# HAS.net
KiCad netlist of a schematic drawn in EAGLE
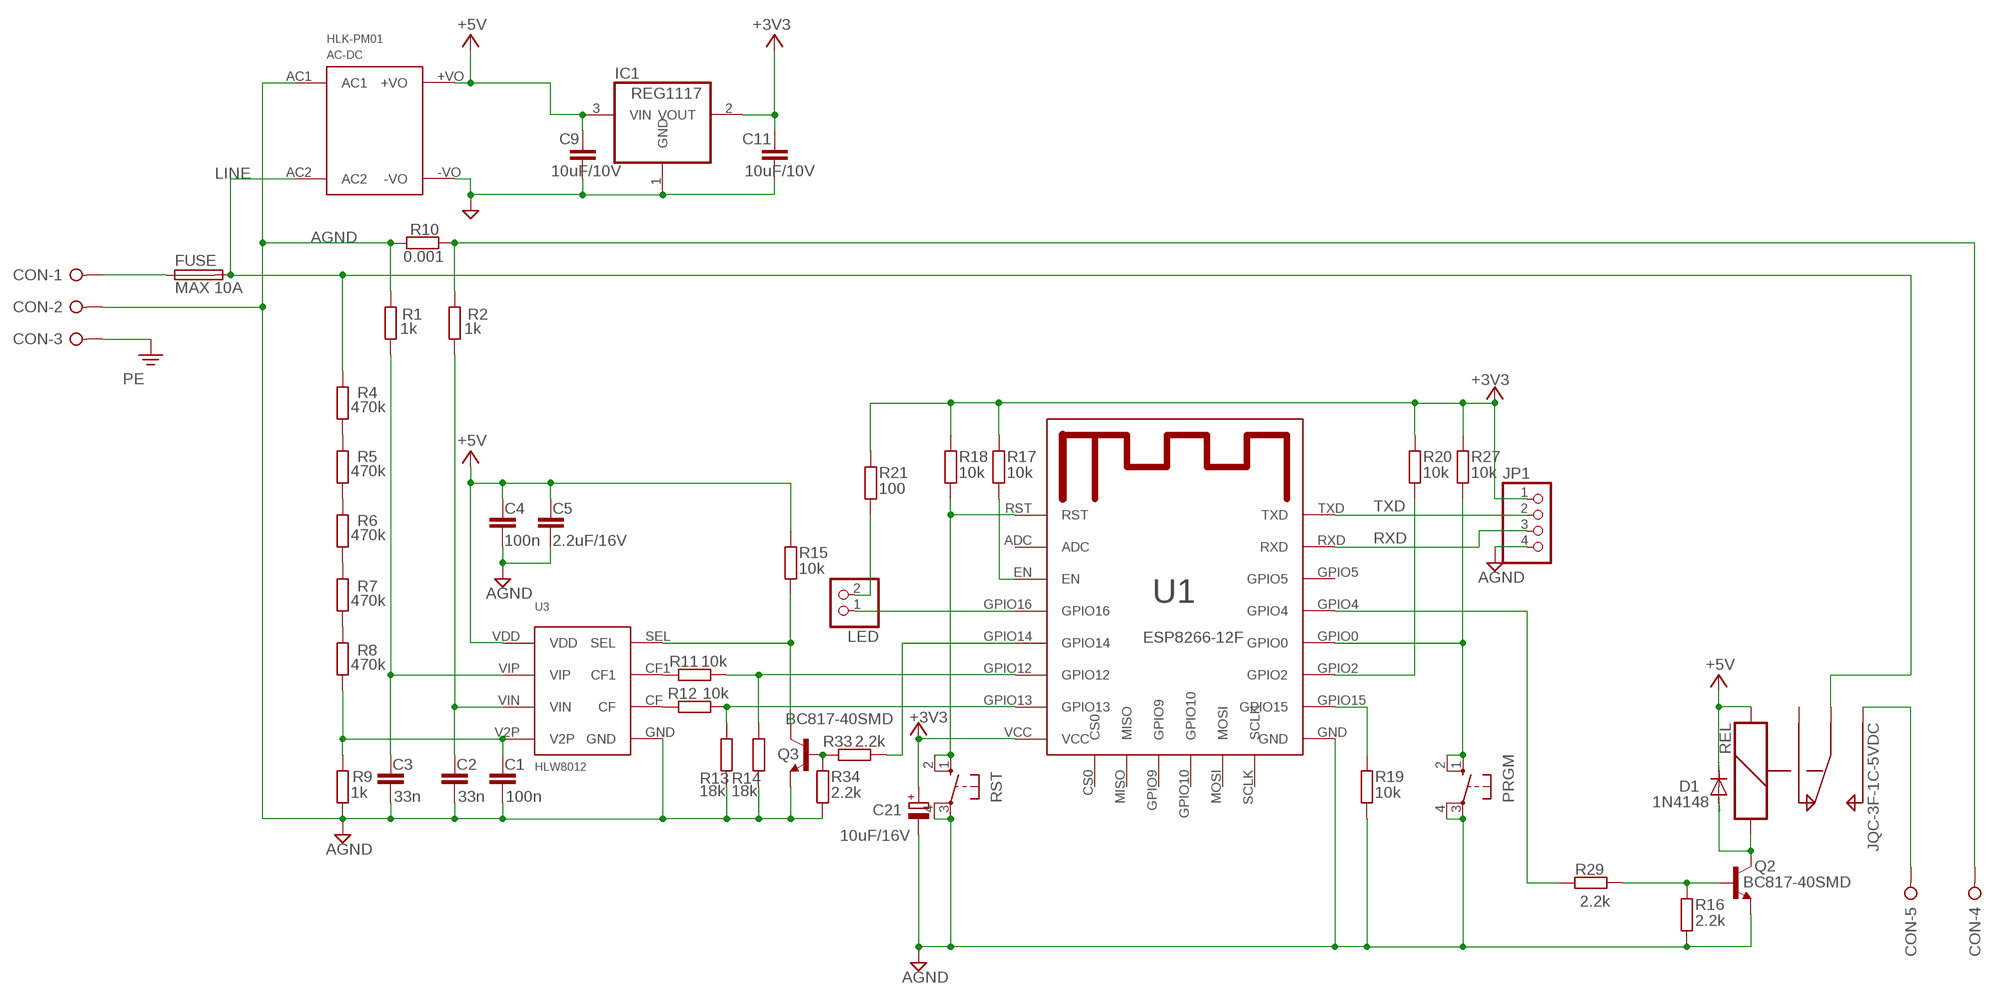
[diagram p0: schematic, sheet 1]

(export (version "E")
  (design (tool "Eeschema 10.0.6"))
  (components
    (comp (ref "AC-DC")
      (value "HLK-PM01")
      (footprint "eagle-import:HLK-PM01")
      (libsource (lib "eagle-import") (part "HLK-PM01"))
    )
    (comp (ref "C1")
      (value "100n")
      (footprint "eagle-import:C0805")
      (libsource (lib "eagle-import") (part "C0805"))
    )
    (comp (ref "C2")
      (value "33n")
      (footprint "eagle-import:C0805")
      (libsource (lib "eagle-import") (part "C0805"))
    )
    (comp (ref "C3")
      (value "33n")
      (footprint "eagle-import:C0805")
      (libsource (lib "eagle-import") (part "C0805"))
    )
    (comp (ref "C4")
      (value "100n")
      (footprint "eagle-import:C0805")
      (libsource (lib "eagle-import") (part "C0805"))
    )
    (comp (ref "C5")
      (value "2.2uF/16V")
      (footprint "eagle-import:C0805")
      (libsource (lib "eagle-import") (part "C0805"))
    )
    (comp (ref "C9")
      (value "10uF/10V")
      (footprint "eagle-import:C1206")
      (libsource (lib "eagle-import") (part "C1206"))
    )
    (comp (ref "C11")
      (value "10uF/10V")
      (footprint "eagle-import:C1206")
      (libsource (lib "eagle-import") (part "C1206"))
    )
    (comp (ref "C21")
      (value "10uF/16V")
      (footprint "eagle-import:SMC_B")
      (libsource (lib "eagle-import") (part "TANT_B"))
    )
    (comp (ref "CON")
      (value "W237-05P")
      (footprint "eagle-import:W237-5P")
      (libsource (lib "eagle-import") (part "W237-05P"))
    )
    (comp (ref "D1")
      (value "1N4148")
      (footprint "eagle-import:SOD123")
      (libsource (lib "eagle-import") (part "DIODE-SOD123"))
    )
    (comp (ref "FUSE")
      (value "MAX 10A")
      (footprint "eagle-import:SH22")
      (libsource (lib "eagle-import") (part "FUSE"))
    )
    (comp (ref "IC1")
      (value "REG1117")
      (footprint "eagle-import:SOT223")
      (libsource (lib "eagle-import") (part "REG1117"))
    )
    (comp (ref "JP1")
      (value "PINHD-1X4")
      (footprint "eagle-import:1X04")
      (libsource (lib "eagle-import") (part "PINHD-1X4"))
    )
    (comp (ref "LED")
      (value "PINHD-1X2")
      (footprint "eagle-import:1X02")
      (libsource (lib "eagle-import") (part "PINHD-1X2"))
    )
    (comp (ref "PRGM")
      (value "10-XX")
      (footprint "eagle-import:B3F-10XX")
      (fields (field (name "MPN") "B3F-1000"))
      (libsource (lib "eagle-import") (part "10-XX"))
    )
    (comp (ref "Q2")
      (value "BC817-40SMD")
      (footprint "eagle-import:SOT23-BEC")
      (libsource (lib "eagle-import") (part "BC817SMD-40"))
    )
    (comp (ref "Q3")
      (value "BC817-40SMD")
      (footprint "eagle-import:SOT23-BEC")
      (libsource (lib "eagle-import") (part "BC817SMD-40"))
    )
    (comp (ref "R1")
      (value "1k")
      (footprint "eagle-import:R0805")
      (libsource (lib "eagle-import") (part "R0805"))
    )
    (comp (ref "R2")
      (value "1k")
      (footprint "eagle-import:R0805")
      (libsource (lib "eagle-import") (part "R0805"))
    )
    (comp (ref "R4")
      (value "470k")
      (footprint "eagle-import:R0805")
      (libsource (lib "eagle-import") (part "R0805"))
    )
    (comp (ref "R5")
      (value "470k")
      (footprint "eagle-import:R0805")
      (libsource (lib "eagle-import") (part "R0805"))
    )
    (comp (ref "R6")
      (value "470k")
      (footprint "eagle-import:R0805")
      (libsource (lib "eagle-import") (part "R0805"))
    )
    (comp (ref "R7")
      (value "470k")
      (footprint "eagle-import:R0805")
      (libsource (lib "eagle-import") (part "R0805"))
    )
    (comp (ref "R8")
      (value "470k")
      (footprint "eagle-import:R0805")
      (libsource (lib "eagle-import") (part "R0805"))
    )
    (comp (ref "R9")
      (value "1k")
      (footprint "eagle-import:R0805")
      (libsource (lib "eagle-import") (part "R0805"))
    )
    (comp (ref "R10")
      (value "0.001")
      (footprint "eagle-import:R2512")
      (fields (field (name "SPICEPREFIX") "R"))
      (libsource (lib "eagle-import") (part "R2512"))
    )
    (comp (ref "R11")
      (value "10k")
      (footprint "eagle-import:R0805")
      (libsource (lib "eagle-import") (part "R0805"))
    )
    (comp (ref "R12")
      (value "10k")
      (footprint "eagle-import:R0805")
      (libsource (lib "eagle-import") (part "R0805"))
    )
    (comp (ref "R13")
      (value "18k")
      (footprint "eagle-import:R0805")
      (libsource (lib "eagle-import") (part "R0805"))
    )
    (comp (ref "R14")
      (value "18k")
      (footprint "eagle-import:R0805")
      (fields (field (name "SPICEPREFIX") "R"))
      (libsource (lib "eagle-import") (part "R0805"))
    )
    (comp (ref "R15")
      (value "10k")
      (footprint "eagle-import:R0805")
      (fields (field (name "SPICEPREFIX") "R"))
      (libsource (lib "eagle-import") (part "R0805"))
    )
    (comp (ref "R16")
      (value "2.2k")
      (footprint "eagle-import:R0805")
      (fields (field (name "SPICEPREFIX") "R"))
      (libsource (lib "eagle-import") (part "R0805"))
    )
    (comp (ref "R17")
      (value "10k")
      (footprint "eagle-import:R0805")
      (fields (field (name "SPICEPREFIX") "R"))
      (libsource (lib "eagle-import") (part "R0805"))
    )
    (comp (ref "R18")
      (value "10k")
      (footprint "eagle-import:R0805")
      (fields (field (name "SPICEPREFIX") "R"))
      (libsource (lib "eagle-import") (part "R0805"))
    )
    (comp (ref "R19")
      (value "10k")
      (footprint "eagle-import:R0805")
      (fields (field (name "SPICEPREFIX") "R"))
      (libsource (lib "eagle-import") (part "R0805"))
    )
    (comp (ref "R20")
      (value "10k")
      (footprint "eagle-import:R0805")
      (fields (field (name "SPICEPREFIX") "R"))
      (libsource (lib "eagle-import") (part "R0805"))
    )
    (comp (ref "R21")
      (value "100")
      (footprint "eagle-import:R0805")
      (fields (field (name "SPICEPREFIX") "R"))
      (libsource (lib "eagle-import") (part "R0805"))
    )
    (comp (ref "R27")
      (value "10k")
      (footprint "eagle-import:R0805")
      (fields (field (name "SPICEPREFIX") "R"))
      (libsource (lib "eagle-import") (part "R0805"))
    )
    (comp (ref "R29")
      (value "2.2k")
      (footprint "eagle-import:R0805")
      (fields (field (name "SPICEPREFIX") "R"))
      (libsource (lib "eagle-import") (part "R0805"))
    )
    (comp (ref "R33")
      (value "2.2k")
      (footprint "eagle-import:R0805")
      (fields (field (name "SPICEPREFIX") "R"))
      (libsource (lib "eagle-import") (part "R0805"))
    )
    (comp (ref "R34")
      (value "2.2k")
      (footprint "eagle-import:R0805")
      (fields (field (name "SPICEPREFIX") "R"))
      (libsource (lib "eagle-import") (part "R0805"))
    )
    (comp (ref "REL")
      (value "JQC-3F-1C-5VDC")
      (footprint "eagle-import:JQC-3F-1C-5VDC")
      (libsource (lib "eagle-import") (part "JQC-3F-1C-5VDC"))
    )
    (comp (ref "RST")
      (value "10-XX")
      (footprint "eagle-import:B3F-10XX")
      (fields (field (name "MPN") "B3F-1000"))
      (libsource (lib "eagle-import") (part "10-XX"))
    )
    (comp (ref "U1")
      (value "ESP8266-12F")
      (footprint "eagle-import:ESP8266-12F")
      (libsource (lib "eagle-import") (part "ESP8266-12F"))
    )
    (comp (ref "U3")
      (value "HLW8012")
      (footprint "eagle-import:HLW8012")
      (libsource (lib "eagle-import") (part "HLW8012"))
    )
  )
  (nets
    (net (code "1") (name "+3V3") (class "Default")
      (node (ref "C11") (pin "2") (pinfunction "2_2") (pintype "passive"))
      (node (ref "C21") (pin "+") (pinfunction "+_+") (pintype "passive"))
      (node (ref "IC1") (pin "2") (pinfunction "VOUT_2") (pintype "output"))
      (node (ref "JP1") (pin "1") (pinfunction "1_1") (pintype "passive"))
      (node (ref "R17") (pin "1") (pinfunction "1_1") (pintype "passive"))
      (node (ref "R18") (pin "1") (pinfunction "1_1") (pintype "passive"))
      (node (ref "R20") (pin "1") (pinfunction "1_1") (pintype "passive"))
      (node (ref "R21") (pin "1") (pinfunction "1_1") (pintype "passive"))
      (node (ref "R27") (pin "1") (pinfunction "1_1") (pintype "passive"))
      (node (ref "U1") (pin "VCC") (pinfunction "VCC_VCC") (pintype "bidirectional"))
    )
    (net (code "2") (name "+5V") (class "Default")
      (node (ref "AC-DC") (pin "+VO") (pinfunction "+VO_+VO") (pintype "bidirectional"))
      (node (ref "C4") (pin "1") (pinfunction "1_1") (pintype "passive"))
      (node (ref "C5") (pin "1") (pinfunction "1_1") (pintype "passive"))
      (node (ref "C9") (pin "2") (pinfunction "2_2") (pintype "passive"))
      (node (ref "D1") (pin "C") (pinfunction "C_C") (pintype "passive"))
      (node (ref "IC1") (pin "3") (pinfunction "VIN_3") (pintype "input"))
      (node (ref "R15") (pin "1") (pinfunction "1_1") (pintype "passive"))
      (node (ref "REL") (pin "R2") (pinfunction "R2_R2") (pintype "passive"))
      (node (ref "U3") (pin "VDD") (pinfunction "VDD_VDD") (pintype "bidirectional"))
    )
    (net (code "3") (name "/LINE") (class "Default")
      (node (ref "AC-DC") (pin "AC2") (pinfunction "AC2_AC2") (pintype "bidirectional"))
      (node (ref "FUSE") (pin "2") (pinfunction "2_2") (pintype "passive"))
      (node (ref "R4") (pin "2") (pinfunction "2_2") (pintype "passive"))
      (node (ref "REL") (pin "COM") (pinfunction "COM_COM") (pintype "passive"))
    )
    (net (code "4") (name "/RXD") (class "Default")
      (node (ref "JP1") (pin "3") (pinfunction "3_3") (pintype "passive"))
      (node (ref "U1") (pin "RXD") (pinfunction "RXD_RXD") (pintype "bidirectional"))
    )
    (net (code "5") (name "/TXD") (class "Default")
      (node (ref "JP1") (pin "2") (pinfunction "2_2") (pintype "passive"))
      (node (ref "U1") (pin "TXD") (pinfunction "TXD_TXD") (pintype "bidirectional"))
    )
    (net (code "6") (name "AGND") (class "Default")
      (node (ref "AC-DC") (pin "-VO") (pinfunction "-VO_-VO") (pintype "bidirectional"))
      (node (ref "AC-DC") (pin "AC1") (pinfunction "AC1_AC1") (pintype "bidirectional"))
      (node (ref "C1") (pin "2") (pinfunction "2_2") (pintype "passive"))
      (node (ref "C11") (pin "1") (pinfunction "1_1") (pintype "passive"))
      (node (ref "C2") (pin "2") (pinfunction "2_2") (pintype "passive"))
      (node (ref "C21") (pin "-") (pinfunction "-_-") (pintype "passive"))
      (node (ref "C3") (pin "2") (pinfunction "2_2") (pintype "passive"))
      (node (ref "C4") (pin "2") (pinfunction "2_2") (pintype "passive"))
      (node (ref "C5") (pin "2") (pinfunction "2_2") (pintype "passive"))
      (node (ref "C9") (pin "1") (pinfunction "1_1") (pintype "passive"))
      (node (ref "CON") (pin "2") (pinfunction "KL_2") (pintype "passive"))
      (node (ref "IC1") (pin "1") (pinfunction "GND_1") (pintype "power_in"))
      (node (ref "JP1") (pin "4") (pinfunction "4_4") (pintype "passive"))
      (node (ref "PRGM") (pin "3") (pinfunction "P_3") (pintype "passive"))
      (node (ref "PRGM") (pin "4") (pinfunction "P1_4") (pintype "passive"))
      (node (ref "Q2") (pin "E") (pinfunction "E_E") (pintype "passive"))
      (node (ref "Q3") (pin "E") (pinfunction "E_E") (pintype "passive"))
      (node (ref "R1") (pin "1") (pinfunction "1_1") (pintype "passive"))
      (node (ref "R10") (pin "1") (pinfunction "1_1") (pintype "passive"))
      (node (ref "R13") (pin "2") (pinfunction "2_2") (pintype "passive"))
      (node (ref "R14") (pin "2") (pinfunction "2_2") (pintype "passive"))
      (node (ref "R16") (pin "2") (pinfunction "2_2") (pintype "passive"))
      (node (ref "R19") (pin "2") (pinfunction "2_2") (pintype "passive"))
      (node (ref "R34") (pin "2") (pinfunction "2_2") (pintype "passive"))
      (node (ref "R9") (pin "1") (pinfunction "1_1") (pintype "passive"))
      (node (ref "RST") (pin "3") (pinfunction "P_3") (pintype "passive"))
      (node (ref "RST") (pin "4") (pinfunction "P1_4") (pintype "passive"))
      (node (ref "U1") (pin "GND") (pinfunction "GND_GND") (pintype "bidirectional"))
      (node (ref "U3") (pin "GND") (pinfunction "GND_GND") (pintype "bidirectional"))
    )
    (net (code "7") (name "Net-(C1-Pad1)") (class "Default")
      (node (ref "C1") (pin "1") (pinfunction "1_1") (pintype "passive"))
      (node (ref "R8") (pin "1") (pinfunction "1_1") (pintype "passive"))
      (node (ref "R9") (pin "2") (pinfunction "2_2") (pintype "passive"))
      (node (ref "U3") (pin "V2P") (pinfunction "V2P_V2P") (pintype "bidirectional"))
    )
    (net (code "8") (name "Net-(C2-Pad1)") (class "Default")
      (node (ref "C2") (pin "1") (pinfunction "1_1") (pintype "passive"))
      (node (ref "R2") (pin "2") (pinfunction "2_2") (pintype "passive"))
      (node (ref "U3") (pin "VIN") (pinfunction "VIN_VIN") (pintype "bidirectional"))
    )
    (net (code "9") (name "Net-(C3-Pad1)") (class "Default")
      (node (ref "C3") (pin "1") (pinfunction "1_1") (pintype "passive"))
      (node (ref "R1") (pin "2") (pinfunction "2_2") (pintype "passive"))
      (node (ref "U3") (pin "VIP") (pinfunction "VIP_VIP") (pintype "bidirectional"))
    )
    (net (code "10") (name "Net-(CONA-KL)") (class "Default")
      (node (ref "CON") (pin "1") (pinfunction "KL_1") (pintype "passive"))
      (node (ref "FUSE") (pin "1") (pinfunction "1_1") (pintype "passive"))
    )
    (net (code "11") (name "Net-(COND-KL)") (class "Default")
      (node (ref "CON") (pin "4") (pinfunction "KL_4") (pintype "passive"))
      (node (ref "R10") (pin "2") (pinfunction "2_2") (pintype "passive"))
      (node (ref "R2") (pin "1") (pinfunction "1_1") (pintype "passive"))
    )
    (net (code "12") (name "Net-(CONE-KL)") (class "Default")
      (node (ref "CON") (pin "5") (pinfunction "KL_5") (pintype "passive"))
      (node (ref "REL") (pin "NO") (pinfunction "NO_NO") (pintype "passive"))
    )
    (net (code "13") (name "Net-(D1-PadA)") (class "Default")
      (node (ref "D1") (pin "A") (pinfunction "A_A") (pintype "passive"))
      (node (ref "Q2") (pin "C") (pinfunction "C_C") (pintype "passive"))
      (node (ref "REL") (pin "R1") (pinfunction "R1_R1") (pintype "passive"))
    )
    (net (code "14") (name "Net-(LED-Pad1)") (class "Default")
      (node (ref "LED") (pin "1") (pinfunction "1_1") (pintype "passive"))
      (node (ref "U1") (pin "GPIO16") (pinfunction "GPIO16_GPIO16") (pintype "bidirectional"))
    )
    (net (code "15") (name "Net-(LED-Pad2)") (class "Default")
      (node (ref "LED") (pin "2") (pinfunction "2_2") (pintype "passive"))
      (node (ref "R21") (pin "2") (pinfunction "2_2") (pintype "passive"))
    )
    (net (code "16") (name "Net-(PRGM-S)") (class "Default")
      (node (ref "PRGM") (pin "1") (pinfunction "S_1") (pintype "passive"))
      (node (ref "PRGM") (pin "2") (pinfunction "S1_2") (pintype "passive"))
      (node (ref "R27") (pin "2") (pinfunction "2_2") (pintype "passive"))
      (node (ref "U1") (pin "GPIO0") (pinfunction "GPIO0_GPIO0") (pintype "bidirectional"))
    )
    (net (code "17") (name "Net-(Q2-PadB)") (class "Default")
      (node (ref "Q2") (pin "B") (pinfunction "B_B") (pintype "passive"))
      (node (ref "R16") (pin "1") (pinfunction "1_1") (pintype "passive"))
      (node (ref "R29") (pin "2") (pinfunction "2_2") (pintype "passive"))
    )
    (net (code "18") (name "Net-(Q3-PadB)") (class "Default")
      (node (ref "Q3") (pin "B") (pinfunction "B_B") (pintype "passive"))
      (node (ref "R33") (pin "2") (pinfunction "2_2") (pintype "passive"))
      (node (ref "R34") (pin "1") (pinfunction "1_1") (pintype "passive"))
    )
    (net (code "19") (name "Net-(Q3-PadC)") (class "Default")
      (node (ref "Q3") (pin "C") (pinfunction "C_C") (pintype "passive"))
      (node (ref "R15") (pin "2") (pinfunction "2_2") (pintype "passive"))
      (node (ref "U3") (pin "SEL") (pinfunction "SEL_SEL") (pintype "bidirectional"))
    )
    (net (code "20") (name "Net-(R4-Pad1)") (class "Default")
      (node (ref "R4") (pin "1") (pinfunction "1_1") (pintype "passive"))
      (node (ref "R5") (pin "2") (pinfunction "2_2") (pintype "passive"))
    )
    (net (code "21") (name "Net-(R5-Pad1)") (class "Default")
      (node (ref "R5") (pin "1") (pinfunction "1_1") (pintype "passive"))
      (node (ref "R6") (pin "2") (pinfunction "2_2") (pintype "passive"))
    )
    (net (code "22") (name "Net-(R6-Pad1)") (class "Default")
      (node (ref "R6") (pin "1") (pinfunction "1_1") (pintype "passive"))
      (node (ref "R7") (pin "2") (pinfunction "2_2") (pintype "passive"))
    )
    (net (code "23") (name "Net-(R7-Pad1)") (class "Default")
      (node (ref "R7") (pin "1") (pinfunction "1_1") (pintype "passive"))
      (node (ref "R8") (pin "2") (pinfunction "2_2") (pintype "passive"))
    )
    (net (code "24") (name "Net-(R11-Pad1)") (class "Default")
      (node (ref "R11") (pin "1") (pinfunction "1_1") (pintype "passive"))
      (node (ref "U3") (pin "CF1") (pinfunction "CF1_CF1") (pintype "bidirectional"))
    )
    (net (code "25") (name "Net-(R11-Pad2)") (class "Default")
      (node (ref "R11") (pin "2") (pinfunction "2_2") (pintype "passive"))
      (node (ref "R14") (pin "1") (pinfunction "1_1") (pintype "passive"))
      (node (ref "U1") (pin "GPIO12") (pinfunction "GPIO12_GPIO12") (pintype "bidirectional"))
    )
    (net (code "26") (name "Net-(R12-Pad1)") (class "Default")
      (node (ref "R12") (pin "1") (pinfunction "1_1") (pintype "passive"))
      (node (ref "U3") (pin "CF") (pinfunction "CF_CF") (pintype "bidirectional"))
    )
    (net (code "27") (name "Net-(R12-Pad2)") (class "Default")
      (node (ref "R12") (pin "2") (pinfunction "2_2") (pintype "passive"))
      (node (ref "R13") (pin "1") (pinfunction "1_1") (pintype "passive"))
      (node (ref "U1") (pin "GPIO13") (pinfunction "GPIO13_GPIO13") (pintype "bidirectional"))
    )
    (net (code "28") (name "Net-(R17-Pad2)") (class "Default")
      (node (ref "R17") (pin "2") (pinfunction "2_2") (pintype "passive"))
      (node (ref "U1") (pin "EN") (pinfunction "EN_EN") (pintype "bidirectional"))
    )
    (net (code "29") (name "Net-(R19-Pad1)") (class "Default")
      (node (ref "R19") (pin "1") (pinfunction "1_1") (pintype "passive"))
      (node (ref "U1") (pin "GPIO15") (pinfunction "GPIO15_GPIO15") (pintype "bidirectional"))
    )
    (net (code "30") (name "Net-(R20-Pad2)") (class "Default")
      (node (ref "R20") (pin "2") (pinfunction "2_2") (pintype "passive"))
      (node (ref "U1") (pin "GPIO2") (pinfunction "GPIO2_GPIO2") (pintype "bidirectional"))
    )
    (net (code "31") (name "Net-(R29-Pad1)") (class "Default")
      (node (ref "R29") (pin "1") (pinfunction "1_1") (pintype "passive"))
      (node (ref "U1") (pin "GPIO4") (pinfunction "GPIO4_GPIO4") (pintype "bidirectional"))
    )
    (net (code "32") (name "Net-(R33-Pad1)") (class "Default")
      (node (ref "R33") (pin "1") (pinfunction "1_1") (pintype "passive"))
      (node (ref "U1") (pin "GPIO14") (pinfunction "GPIO14_GPIO14") (pintype "bidirectional"))
    )
    (net (code "33") (name "Net-(RST-S)") (class "Default")
      (node (ref "R18") (pin "2") (pinfunction "2_2") (pintype "passive"))
      (node (ref "RST") (pin "1") (pinfunction "S_1") (pintype "passive"))
      (node (ref "RST") (pin "2") (pinfunction "S1_2") (pintype "passive"))
      (node (ref "U1") (pin "RST") (pinfunction "RST_RST") (pintype "bidirectional"))
    )
    (net (code "34") (name "PE") (class "Default")
      (node (ref "CON") (pin "3") (pinfunction "KL_3") (pintype "passive"))
    )
    (net (code "35") (name "unconnected-(REL-PadNC)") (class "Default")
      (node (ref "REL") (pin "NC") (pinfunction "NC_NC") (pintype "passive"))
    )
    (net (code "36") (name "unconnected-(U1-PadADC)") (class "Default")
      (node (ref "U1") (pin "ADC") (pinfunction "ADC_ADC") (pintype "bidirectional"))
    )
    (net (code "37") (name "unconnected-(U1-PadCS0)") (class "Default")
      (node (ref "U1") (pin "CS0") (pinfunction "CS0_CS0") (pintype "bidirectional"))
    )
    (net (code "38") (name "unconnected-(U1-PadGPIO5)") (class "Default")
      (node (ref "U1") (pin "GPIO5") (pinfunction "GPIO5_GPIO5") (pintype "bidirectional"))
    )
    (net (code "39") (name "unconnected-(U1-PadGPIO9)") (class "Default")
      (node (ref "U1") (pin "GPIO9") (pinfunction "GPIO9_GPIO9") (pintype "bidirectional"))
    )
    (net (code "40") (name "unconnected-(U1-PadGPIO10)") (class "Default")
      (node (ref "U1") (pin "GPIO10") (pinfunction "GPIO10_GPIO10") (pintype "bidirectional"))
    )
    (net (code "41") (name "unconnected-(U1-PadMISO)") (class "Default")
      (node (ref "U1") (pin "MISO") (pinfunction "MISO_MISO") (pintype "bidirectional"))
    )
    (net (code "42") (name "unconnected-(U1-PadMOSI)") (class "Default")
      (node (ref "U1") (pin "MOSI") (pinfunction "MOSI_MOSI") (pintype "bidirectional"))
    )
    (net (code "43") (name "unconnected-(U1-PadSCLK)") (class "Default")
      (node (ref "U1") (pin "SCLK") (pinfunction "SCLK_SCLK") (pintype "bidirectional"))
    )
  )
)
